# 1_Power.net
KiCad netlist of a schematic drawn in Altium Designer
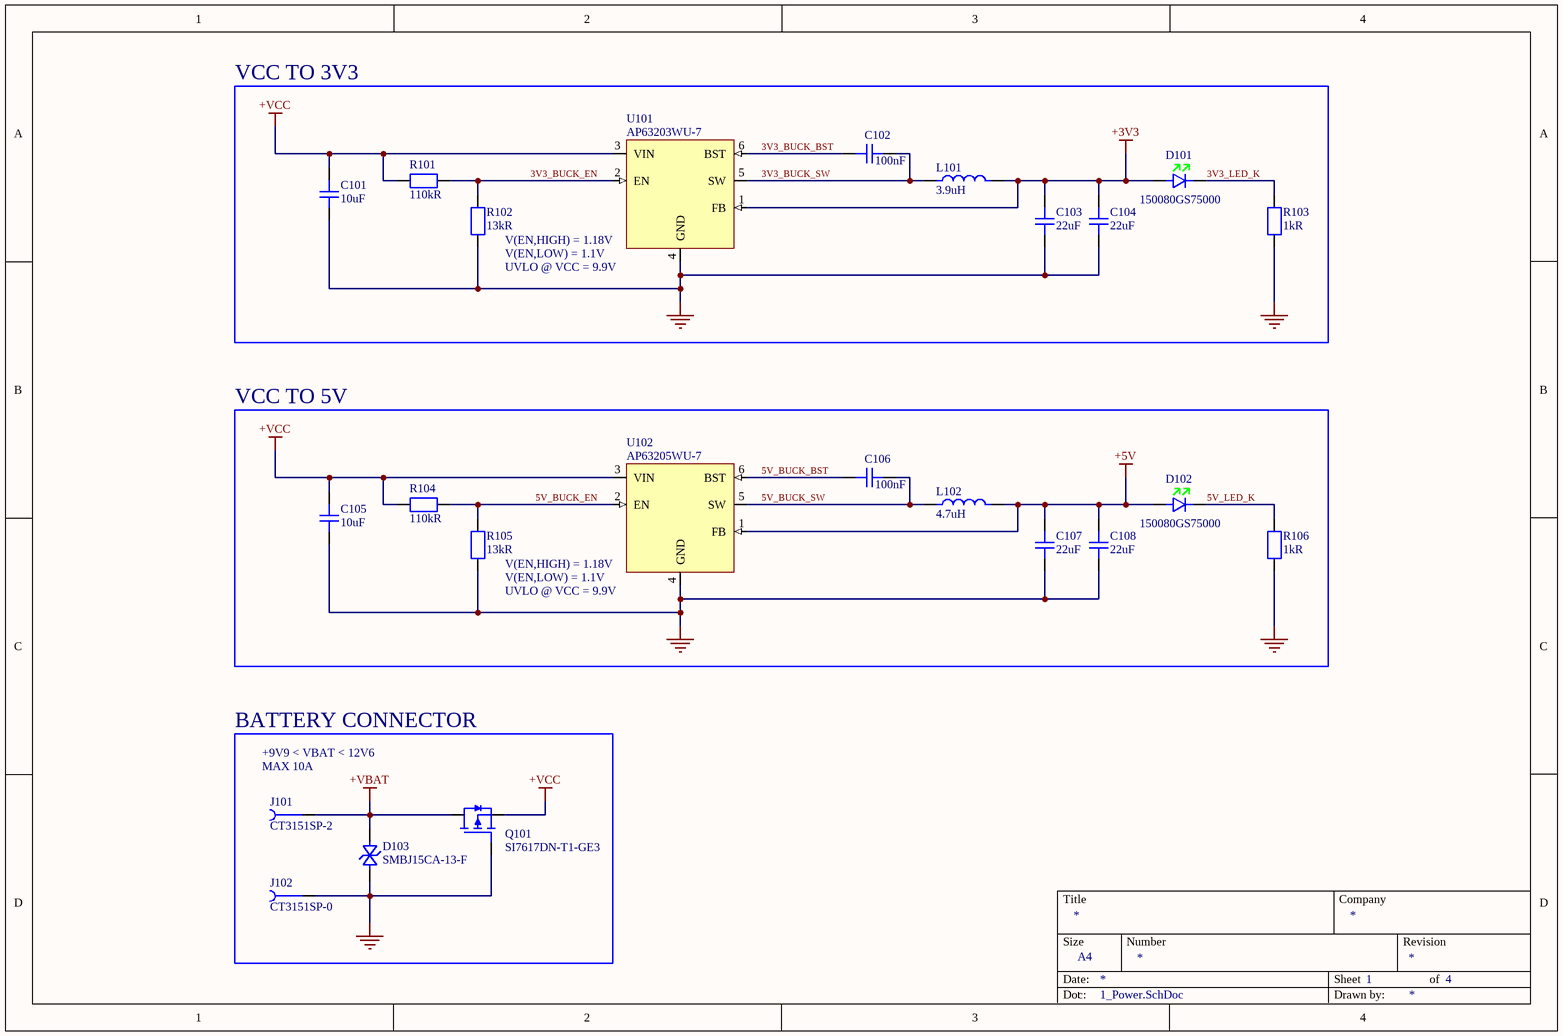
[diagram p0: 1_Power.SchDoc]

(export (version "E")
  (design (tool "Eeschema 10.0.6"))
  (components
    (comp (ref "C101")
      (value "10uF")
      (footprint "C_Yageo_CC_0805_A")
      (description "0805 10 uF 16 V ±10% Tolerance X5R Multilayer Ceramic Chip Capacitor")
      (fields (field (name "TOLERANCE") "10%") (field (name "LCSC PART NUMBER") "C2982567"))
      (libsource (lib "Dennis Micro Computers") (part "C"))
    )
    (comp (ref "C102")
      (value "100nF")
      (footprint "C_Yageo_CC_0402_A")
      (description "Multilayer Ceramic Capacitor, 0.1 uF, 10 V, ± 20%, X7R, 0402 [1005 Metric]")
      (fields (field (name "TOLERANCE") "20%") (field (name "LCSC PART NUMBER") "C2171572"))
      (libsource (lib "Dennis Micro Computers") (part "C"))
    )
    (comp (ref "C103")
      (value "22uF")
      (footprint "C_Yageo_CC_0805_A")
      (description "Multilayer Ceramic Capacitor, 22 uF, 10 V, ± 20%, X5R, 0805 [2012 Metric]")
      (fields (field (name "TOLERANCE") "20%") (field (name "LCSC PART NUMBER") "C109314"))
      (libsource (lib "Dennis Micro Computers") (part "C"))
    )
    (comp (ref "C104")
      (value "22uF")
      (footprint "C_Yageo_CC_0805_A")
      (description "Multilayer Ceramic Capacitor, 22 uF, 10 V, ± 20%, X5R, 0805 [2012 Metric]")
      (fields (field (name "TOLERANCE") "20%") (field (name "LCSC PART NUMBER") "C109314"))
      (libsource (lib "Dennis Micro Computers") (part "C"))
    )
    (comp (ref "C105")
      (value "10uF")
      (footprint "C_Yageo_CC_0805_A")
      (description "0805 10 uF 16 V ±10% Tolerance X5R Multilayer Ceramic Chip Capacitor")
      (fields (field (name "TOLERANCE") "10%") (field (name "LCSC PART NUMBER") "C2982567"))
      (libsource (lib "Dennis Micro Computers") (part "C"))
    )
    (comp (ref "C106")
      (value "100nF")
      (footprint "C_Yageo_CC_0402_A")
      (description "Multilayer Ceramic Capacitor, 0.1 uF, 10 V, ± 20%, X7R, 0402 [1005 Metric]")
      (fields (field (name "TOLERANCE") "20%") (field (name "LCSC PART NUMBER") "C2171572"))
      (libsource (lib "Dennis Micro Computers") (part "C"))
    )
    (comp (ref "C107")
      (value "22uF")
      (footprint "C_Yageo_CC_0805_A")
      (description "Multilayer Ceramic Capacitor, 22 uF, 10 V, ± 20%, X5R, 0805 [2012 Metric]")
      (fields (field (name "TOLERANCE") "20%") (field (name "LCSC PART NUMBER") "C109314"))
      (libsource (lib "Dennis Micro Computers") (part "C"))
    )
    (comp (ref "C108")
      (value "22uF")
      (footprint "C_Yageo_CC_0805_A")
      (description "Multilayer Ceramic Capacitor, 22 uF, 10 V, ± 20%, X5R, 0805 [2012 Metric]")
      (fields (field (name "TOLERANCE") "20%") (field (name "LCSC PART NUMBER") "C109314"))
      (libsource (lib "Dennis Micro Computers") (part "C"))
    )
    (comp (ref "D101")
      (value "150080GS75000")
      (footprint "D_LED_We_150080GS75000")
      (description "WURTH ELEKTRONIK - 150080GS75000 - LED, Green, SMD, 0805, 30 mA, 3.2 V, 520 nm")
      (fields (field (name "LCSC PART NUMBER") "C2890404"))
      (libsource (lib "Dennis Micro Computers") (part "D_LED_Green"))
    )
    (comp (ref "D102")
      (value "150080GS75000")
      (footprint "D_LED_We_150080GS75000")
      (description "WURTH ELEKTRONIK - 150080GS75000 - LED, Green, SMD, 0805, 30 mA, 3.2 V, 520 nm")
      (fields (field (name "LCSC PART NUMBER") "C2890404"))
      (libsource (lib "Dennis Micro Computers") (part "D_LED_Green"))
    )
    (comp (ref "D103")
      (value "SMBJ15CA-13-F")
      (footprint "D_TVS_BI_Diodes_SMBJ15CA-13-F_A")
      (description "Tvs Diode, Bidir, 15V, 600W, Do-214Aa Rohs Compliant: Yes")
      (fields (field (name "LCSC PART NUMBER") "C135047"))
      (libsource (lib "Dennis Micro Computers") (part "D_TVS_Bi"))
    )
    (comp (ref "J101")
      (value "CT3151SP-2")
      (footprint "J_CalTest_CT3151SP-2")
      (description "Conn 4mm Safety Banana Jack F 1 POS Solder RA Thru-Hole 1 Port Bag")
      (fields (field (name "LCSC PART NUMBER") "Null"))
      (libsource (lib "Dennis Micro Computers") (part "J_01x01_Socket"))
    )
    (comp (ref "J102")
      (value "CT3151SP-0")
      (footprint "J_CalTest_CT3151SP-0")
      (description "Conn 4mm Safety Banana Jack F 1 POS Solder RA Thru-Hole 1 Port Bag")
      (fields (field (name "LCSC PART NUMBER") "Null"))
      (libsource (lib "Dennis Micro Computers") (part "J_01x01_Socket"))
    )
    (comp (ref "L101")
      (value "3.9uH")
      (footprint "L_Murata_1255AY-XXXX=P3")
      (description "Inductor Power Shielded Wirewound 3.9uH 30% 100KHz Ferrite 4.2A 0.0264Ohm DCR 2424 T/R")
      (fields (field (name "TOLERANCE") "30%") (field (name "LCSC PART NUMBER") "C5868202"))
      (libsource (lib "Dennis Micro Computers") (part "L"))
    )
    (comp (ref "L102")
      (value "4.7uH")
      (footprint "L_Murata_1255AY-XXXX=P3")
      (description "Inductor Power Shielded Wirewound 4.7uH 20% 100KHz Ferrite 4A 0.0276Ohm DCR 2424 T/R")
      (fields (field (name "TOLERANCE") "20%") (field (name "LCSC PART NUMBER") "C160951"))
      (libsource (lib "Dennis Micro Computers") (part "L"))
    )
    (comp (ref "Q101")
      (value "SI7617DN-T1-GE3")
      (footprint "Q_Vishay_PowerPACK-1212-8")
      (fields (field (name "LCSC PART NUMBER") "C727607"))
      (libsource (lib "Dennis Micro Computers") (part "Q_PMOS"))
    )
    (comp (ref "R101")
      (value "110kR")
      (footprint "R_Yageo_RCL_0402_A")
      (description "SMD Chip Resistor, 110 kOhm, ± 1%, 63 mW, 0402 [1005 Metric], Thick Film, General Purpose")
      (fields (field (name "TOLERANCE") "1%") (field (name "LCSC PART NUMBER") "C138065"))
      (libsource (lib "Dennis Micro Computers") (part "R"))
    )
    (comp (ref "R102")
      (value "13kR")
      (footprint "R_Yageo_RCL_0402_A")
      (description "SMD Chip Resistor, 13 kOhm, ± 1%, 63 mW, 0402 [1005 Metric], Thick Film, General Purpose")
      (fields (field (name "TOLERANCE") "1%") (field (name "LCSC PART NUMBER") "C138057"))
      (libsource (lib "Dennis Micro Computers") (part "R"))
    )
    (comp (ref "R103")
      (value "1kR")
      (footprint "R_Yageo_RCL_0402_A")
      (description "SMD Chip Resistor, 1 kOhm, ± 1%, 62.5 mW, 0402 [1005 Metric], Thick Film, General Purpose")
      (fields (field (name "TOLERANCE") "1%") (field (name "LCSC PART NUMBER") "C106235"))
      (libsource (lib "Dennis Micro Computers") (part "R"))
    )
    (comp (ref "R104")
      (value "110kR")
      (footprint "R_Yageo_RCL_0402_A")
      (description "SMD Chip Resistor, 110 kOhm, ± 1%, 63 mW, 0402 [1005 Metric], Thick Film, General Purpose")
      (fields (field (name "TOLERANCE") "1%") (field (name "LCSC PART NUMBER") "C138065"))
      (libsource (lib "Dennis Micro Computers") (part "R"))
    )
    (comp (ref "R105")
      (value "13kR")
      (footprint "R_Yageo_RCL_0402_A")
      (description "SMD Chip Resistor, 13 kOhm, ± 1%, 63 mW, 0402 [1005 Metric], Thick Film, General Purpose")
      (fields (field (name "TOLERANCE") "1%") (field (name "LCSC PART NUMBER") "C138057"))
      (libsource (lib "Dennis Micro Computers") (part "R"))
    )
    (comp (ref "R106")
      (value "1kR")
      (footprint "R_Yageo_RCL_0402_A")
      (description "SMD Chip Resistor, 1 kOhm, ± 1%, 62.5 mW, 0402 [1005 Metric], Thick Film, General Purpose")
      (fields (field (name "TOLERANCE") "1%") (field (name "LCSC PART NUMBER") "C106235"))
      (libsource (lib "Dennis Micro Computers") (part "R"))
    )
    (comp (ref "U101")
      (value "AP63203WU-7")
      (footprint "U_Diodes_AP623xx")
      (description "AP63203 Series 3.3 V 2 A SMT Fixed Low IQ Synchronous Buck - TSOT-26")
      (fields (field (name "LCSC PART NUMBER") "C780769"))
      (libsource (lib "Dennis Micro Computers") (part "U_AP632XX"))
    )
    (comp (ref "U102")
      (value "AP63205WU-7")
      (footprint "U_Diodes_AP623xx")
      (description "AP63205 Series 32 V 2 A 1.1 MHz Synchronous Buck Converter -TSOT-26")
      (fields (field (name "LCSC PART NUMBER") "C2071056"))
      (libsource (lib "Dennis Micro Computers") (part "U_AP632XX"))
    )
  )
  (nets
    (net (code "1") (name "+3V3") (class "Default")
      (node (ref "C103") (pin "2") (pinfunction "2_2") (pintype "passive"))
      (node (ref "C104") (pin "2") (pinfunction "2_2") (pintype "passive"))
      (node (ref "D101") (pin "1") (pinfunction "1_1") (pintype "passive"))
      (node (ref "L101") (pin "2") (pinfunction "2_2") (pintype "passive"))
      (node (ref "U101") (pin "1") (pinfunction "FB_1") (pintype "input"))
    )
    (net (code "2") (name "+5V") (class "Default")
      (node (ref "C107") (pin "2") (pinfunction "2_2") (pintype "passive"))
      (node (ref "C108") (pin "2") (pinfunction "2_2") (pintype "passive"))
      (node (ref "D102") (pin "1") (pinfunction "1_1") (pintype "passive"))
      (node (ref "L102") (pin "2") (pinfunction "2_2") (pintype "passive"))
      (node (ref "U102") (pin "1") (pinfunction "FB_1") (pintype "input"))
    )
    (net (code "3") (name "+VBAT") (class "Default")
      (node (ref "D103") (pin "1") (pinfunction "1_1") (pintype "passive"))
      (node (ref "J101") (pin "1") (pinfunction "1_1") (pintype "passive"))
      (node (ref "Q101") (pin "1") (pinfunction "D_1") (pintype "passive"))
    )
    (net (code "4") (name "+VCC") (class "Default")
      (node (ref "C101") (pin "2") (pinfunction "2_2") (pintype "passive"))
      (node (ref "C105") (pin "2") (pinfunction "2_2") (pintype "passive"))
      (node (ref "Q101") (pin "3") (pinfunction "S_3") (pintype "passive"))
      (node (ref "R101") (pin "2") (pinfunction "2_2") (pintype "passive"))
      (node (ref "R104") (pin "2") (pinfunction "2_2") (pintype "passive"))
      (node (ref "U101") (pin "3") (pinfunction "VIN_3") (pintype "power_in"))
      (node (ref "U102") (pin "3") (pinfunction "VIN_3") (pintype "power_in"))
    )
    (net (code "5") (name "/3V3_BUCK_BST") (class "Default")
      (node (ref "C102") (pin "2") (pinfunction "2_2") (pintype "passive"))
      (node (ref "U101") (pin "6") (pinfunction "BST_6") (pintype "input"))
    )
    (net (code "6") (name "/3V3_BUCK_EN") (class "Default")
      (node (ref "R101") (pin "1") (pinfunction "1_1") (pintype "passive"))
      (node (ref "R102") (pin "2") (pinfunction "2_2") (pintype "passive"))
      (node (ref "U101") (pin "2") (pinfunction "EN_2") (pintype "input"))
    )
    (net (code "7") (name "/3V3_BUCK_SW") (class "Default")
      (node (ref "C102") (pin "1") (pinfunction "1_1") (pintype "passive"))
      (node (ref "L101") (pin "1") (pinfunction "1_1") (pintype "passive"))
      (node (ref "U101") (pin "5") (pinfunction "SW_5") (pintype "power_in"))
    )
    (net (code "8") (name "/3V3_LED_K") (class "Default")
      (node (ref "D101") (pin "2") (pinfunction "2_2") (pintype "passive"))
      (node (ref "R103") (pin "2") (pinfunction "2_2") (pintype "passive"))
    )
    (net (code "9") (name "/5V_BUCK_BST") (class "Default")
      (node (ref "C106") (pin "2") (pinfunction "2_2") (pintype "passive"))
      (node (ref "U102") (pin "6") (pinfunction "BST_6") (pintype "input"))
    )
    (net (code "10") (name "/5V_BUCK_EN") (class "Default")
      (node (ref "R104") (pin "1") (pinfunction "1_1") (pintype "passive"))
      (node (ref "R105") (pin "2") (pinfunction "2_2") (pintype "passive"))
      (node (ref "U102") (pin "2") (pinfunction "EN_2") (pintype "input"))
    )
    (net (code "11") (name "/5V_BUCK_SW") (class "Default")
      (node (ref "C106") (pin "1") (pinfunction "1_1") (pintype "passive"))
      (node (ref "L102") (pin "1") (pinfunction "1_1") (pintype "passive"))
      (node (ref "U102") (pin "5") (pinfunction "SW_5") (pintype "power_in"))
    )
    (net (code "12") (name "/5V_LED_K") (class "Default")
      (node (ref "D102") (pin "2") (pinfunction "2_2") (pintype "passive"))
      (node (ref "R106") (pin "2") (pinfunction "2_2") (pintype "passive"))
    )
    (net (code "13") (name "GND") (class "Default")
      (node (ref "C101") (pin "1") (pinfunction "1_1") (pintype "passive"))
      (node (ref "C103") (pin "1") (pinfunction "1_1") (pintype "passive"))
      (node (ref "C104") (pin "1") (pinfunction "1_1") (pintype "passive"))
      (node (ref "C105") (pin "1") (pinfunction "1_1") (pintype "passive"))
      (node (ref "C107") (pin "1") (pinfunction "1_1") (pintype "passive"))
      (node (ref "C108") (pin "1") (pinfunction "1_1") (pintype "passive"))
      (node (ref "D103") (pin "2") (pinfunction "2_2") (pintype "passive"))
      (node (ref "J102") (pin "1") (pinfunction "1_1") (pintype "passive"))
      (node (ref "Q101") (pin "2") (pinfunction "G_2") (pintype "passive"))
      (node (ref "R102") (pin "1") (pinfunction "1_1") (pintype "passive"))
      (node (ref "R103") (pin "1") (pinfunction "1_1") (pintype "passive"))
      (node (ref "R105") (pin "1") (pinfunction "1_1") (pintype "passive"))
      (node (ref "R106") (pin "1") (pinfunction "1_1") (pintype "passive"))
      (node (ref "U101") (pin "4") (pinfunction "GND_4") (pintype "power_in"))
      (node (ref "U102") (pin "4") (pinfunction "GND_4") (pintype "power_in"))
    )
  )
)
